# Arduino-DRA818V-TX.net
KiCad netlist of a schematic drawn in EAGLE
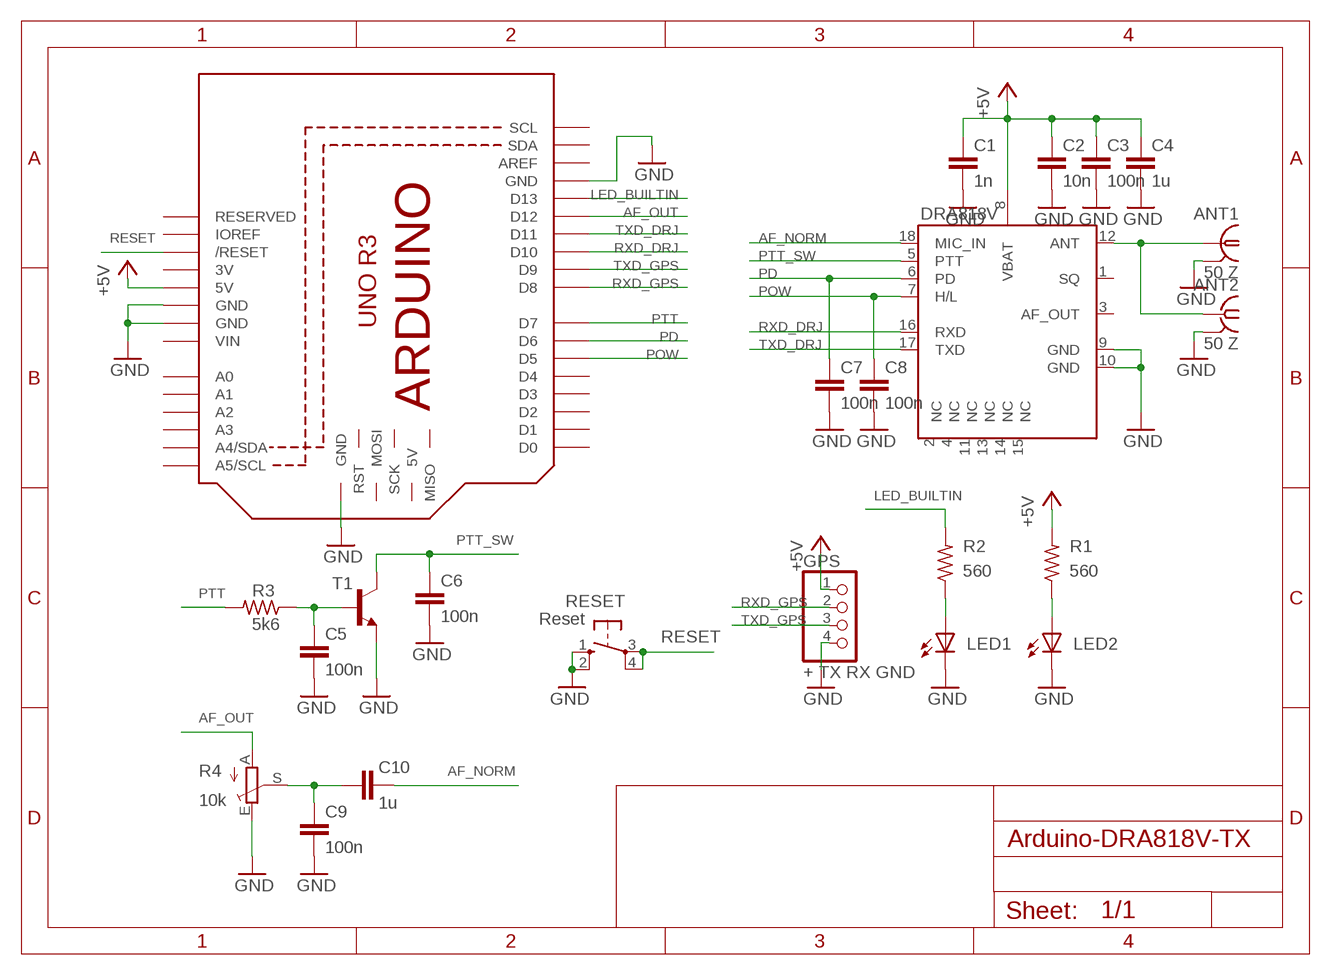
[diagram p0: schematic, sheet 1]

(export (version "E")
  (design (tool "Eeschema 10.0.6"))
  (components
    (comp (ref "ANT1")
      (value "50 Z")
      (footprint "eagle-import:LTI-SASF54GT")
      (libsource (lib "eagle-import") (part "LTI-SASF54GT"))
    )
    (comp (ref "ANT2")
      (value "50 Z")
      (footprint "eagle-import:J502-ND-142-0701-801_806")
      (fields (field (name "MF") "JOHNSON COMPONENTS") (field (name "MPN") "142-0701-801"))
      (libsource (lib "eagle-import") (part "SMA-142-0701-801/806"))
    )
    (comp (ref "C1")
      (value "1n")
      (footprint "eagle-import:C0805")
      (libsource (lib "eagle-import") (part "C-EUC0805"))
    )
    (comp (ref "C2")
      (value "10n")
      (footprint "eagle-import:C0805")
      (libsource (lib "eagle-import") (part "C-EUC0805"))
    )
    (comp (ref "C3")
      (value "100n")
      (footprint "eagle-import:C0805")
      (libsource (lib "eagle-import") (part "C-EUC0805"))
    )
    (comp (ref "C4")
      (value "1u")
      (footprint "eagle-import:C0805")
      (libsource (lib "eagle-import") (part "C-EUC0805"))
    )
    (comp (ref "C5")
      (value "100n")
      (footprint "eagle-import:C0805")
      (libsource (lib "eagle-import") (part "C-EUC0805"))
    )
    (comp (ref "C6")
      (value "100n")
      (footprint "eagle-import:C0805")
      (libsource (lib "eagle-import") (part "C-EUC0805"))
    )
    (comp (ref "C7")
      (value "100n")
      (footprint "eagle-import:C0805")
      (libsource (lib "eagle-import") (part "C-EUC0805"))
    )
    (comp (ref "C8")
      (value "100n")
      (footprint "eagle-import:C0805")
      (libsource (lib "eagle-import") (part "C-EUC0805"))
    )
    (comp (ref "C9")
      (value "100n")
      (footprint "eagle-import:C0805")
      (libsource (lib "eagle-import") (part "C-EUC0805"))
    )
    (comp (ref "C10")
      (value "1u")
      (footprint "eagle-import:C0805")
      (libsource (lib "eagle-import") (part "C-EUC0805"))
    )
    (comp (ref "DRA818V")
      (value "DRA818A")
      (footprint "eagle-import:DRA818A")
      (libsource (lib "eagle-import") (part "DRA818A"))
    )
    (comp (ref "GPS")
      (value "+ TX RX GND")
      (footprint "eagle-import:1X04")
      (libsource (lib "eagle-import") (part "PINHD-1X4"))
    )
    (comp (ref "LED1")
      (value "LED3MM")
      (footprint "eagle-import:LED3MM")
      (libsource (lib "eagle-import") (part "LED3MM"))
    )
    (comp (ref "LED2")
      (value "LED3MM")
      (footprint "eagle-import:LED3MM")
      (libsource (lib "eagle-import") (part "LED3MM"))
    )
    (comp (ref "M1")
      (value "ARDUINO_R3_ICSP")
      (footprint "eagle-import:ARDUINOR3_ICSP")
      (libsource (lib "eagle-import") (part "ARDUINO_R3_ICSP"))
    )
    (comp (ref "R1")
      (value "560")
      (footprint "eagle-import:R0805")
      (libsource (lib "eagle-import") (part "R-US_R0805"))
    )
    (comp (ref "R2")
      (value "560")
      (footprint "eagle-import:R0805")
      (libsource (lib "eagle-import") (part "R-US_R0805"))
    )
    (comp (ref "R3")
      (value "5k6")
      (footprint "eagle-import:R0805")
      (libsource (lib "eagle-import") (part "R-US_R0805"))
    )
    (comp (ref "R4")
      (value "10k")
      (footprint "eagle-import:CA6V")
      (libsource (lib "eagle-import") (part "TRIM_EU-CA6V"))
    )
    (comp (ref "RESET")
      (value "Reset")
      (footprint "eagle-import:B3F-10XX")
      (fields (field (name "MPN") "B3F-1000"))
      (libsource (lib "eagle-import") (part "10-XX"))
    )
    (comp (ref "T1")
      (value "MMBT3904LT1-NPN-SOT23-BEC")
      (footprint "eagle-import:SOT23-BEC")
      (libsource (lib "eagle-import") (part "-NPN-SOT23-BECMMBT3904LT1"))
    )
  )
  (nets
    (net (code "1") (name "+5V") (class "Default")
      (node (ref "C1") (pin "1") (pinfunction "1_1") (pintype "passive"))
      (node (ref "C2") (pin "1") (pinfunction "1_1") (pintype "passive"))
      (node (ref "C3") (pin "1") (pinfunction "1_1") (pintype "passive"))
      (node (ref "C4") (pin "1") (pinfunction "1_1") (pintype "passive"))
      (node (ref "DRA818V") (pin "8") (pinfunction "VBAT_8") (pintype "bidirectional"))
      (node (ref "GPS") (pin "1") (pinfunction "1_1") (pintype "passive"))
      (node (ref "M1") (pin "5V") (pinfunction "5V_5V") (pintype "power_in"))
      (node (ref "R1") (pin "2") (pinfunction "2_2") (pintype "passive"))
    )
    (net (code "2") (name "/3V") (class "Default")
      (node (ref "M1") (pin "3V") (pinfunction "3V_3V") (pintype "power_in"))
    )
    (net (code "3") (name "/AF_NORM") (class "Default")
      (node (ref "C10") (pin "2") (pinfunction "2_2") (pintype "passive"))
      (node (ref "DRA818V") (pin "18") (pinfunction "MIC_IN_18") (pintype "bidirectional"))
    )
    (net (code "4") (name "/AF_OUT") (class "Default")
      (node (ref "M1") (pin "D12") (pinfunction "D12_D12") (pintype "bidirectional"))
      (node (ref "R4") (pin "A") (pinfunction "A_A") (pintype "passive"))
    )
    (net (code "5") (name "/LED_BUILTIN") (class "Default")
      (node (ref "M1") (pin "D13") (pinfunction "D13_D13") (pintype "bidirectional"))
      (node (ref "R2") (pin "2") (pinfunction "2_2") (pintype "passive"))
    )
    (net (code "6") (name "/PD") (class "Default")
      (node (ref "C7") (pin "1") (pinfunction "1_1") (pintype "passive"))
      (node (ref "DRA818V") (pin "6") (pinfunction "PD_6") (pintype "bidirectional"))
      (node (ref "M1") (pin "D6") (pinfunction "D6_D6") (pintype "bidirectional"))
    )
    (net (code "7") (name "/POW") (class "Default")
      (node (ref "C8") (pin "1") (pinfunction "1_1") (pintype "passive"))
      (node (ref "DRA818V") (pin "7") (pinfunction "H/L_7") (pintype "bidirectional"))
      (node (ref "M1") (pin "D5") (pinfunction "D5_D5") (pintype "bidirectional"))
    )
    (net (code "8") (name "/PTT") (class "Default")
      (node (ref "M1") (pin "D7") (pinfunction "D7_D7") (pintype "bidirectional"))
      (node (ref "R3") (pin "2") (pinfunction "2_2") (pintype "passive"))
    )
    (net (code "9") (name "/PTT_SW") (class "Default")
      (node (ref "C6") (pin "1") (pinfunction "1_1") (pintype "passive"))
      (node (ref "DRA818V") (pin "5") (pinfunction "PTT_5") (pintype "bidirectional"))
      (node (ref "T1") (pin "C") (pinfunction "C_C") (pintype "passive"))
    )
    (net (code "10") (name "/RESET") (class "Default")
      (node (ref "M1") (pin "RESET") (pinfunction "/RESET_RESET") (pintype "bidirectional"))
      (node (ref "RESET") (pin "3") (pinfunction "P_3") (pintype "passive"))
      (node (ref "RESET") (pin "4") (pinfunction "P1_4") (pintype "passive"))
    )
    (net (code "11") (name "/RXD_DRJ") (class "Default")
      (node (ref "DRA818V") (pin "16") (pinfunction "RXD_16") (pintype "bidirectional"))
      (node (ref "M1") (pin "D10") (pinfunction "D10_D10") (pintype "bidirectional"))
    )
    (net (code "12") (name "/RXD_GPS") (class "Default")
      (node (ref "GPS") (pin "2") (pinfunction "2_2") (pintype "passive"))
      (node (ref "M1") (pin "D8") (pinfunction "D8_D8") (pintype "bidirectional"))
    )
    (net (code "13") (name "/TXD_DRJ") (class "Default")
      (node (ref "DRA818V") (pin "17") (pinfunction "TXD_17") (pintype "bidirectional"))
      (node (ref "M1") (pin "D11") (pinfunction "D11_D11") (pintype "bidirectional"))
    )
    (net (code "14") (name "/TXD_GPS") (class "Default")
      (node (ref "GPS") (pin "3") (pinfunction "3_3") (pintype "passive"))
      (node (ref "M1") (pin "D9") (pinfunction "D9_D9") (pintype "bidirectional"))
    )
    (net (code "15") (name "/VIN") (class "Default")
      (node (ref "M1") (pin "VIN") (pinfunction "VIN_VIN") (pintype "power_in"))
    )
    (net (code "16") (name "GND") (class "Default")
      (node (ref "ANT1") (pin "2") (pinfunction "2_2") (pintype "passive"))
      (node (ref "ANT1") (pin "3") (pinfunction "2_3") (pintype "passive"))
      (node (ref "ANT1") (pin "4") (pinfunction "2_4") (pintype "passive"))
      (node (ref "ANT1") (pin "5") (pinfunction "2_5") (pintype "passive"))
      (node (ref "ANT2") (pin "G@1") (pinfunction "2_G@1") (pintype "passive"))
      (node (ref "ANT2") (pin "G@2") (pinfunction "2_G@2") (pintype "passive"))
      (node (ref "ANT2") (pin "G@3") (pinfunction "2_G@3") (pintype "passive"))
      (node (ref "ANT2") (pin "G@4") (pinfunction "2_G@4") (pintype "passive"))
      (node (ref "C1") (pin "2") (pinfunction "2_2") (pintype "passive"))
      (node (ref "C2") (pin "2") (pinfunction "2_2") (pintype "passive"))
      (node (ref "C3") (pin "2") (pinfunction "2_2") (pintype "passive"))
      (node (ref "C4") (pin "2") (pinfunction "2_2") (pintype "passive"))
      (node (ref "C5") (pin "2") (pinfunction "2_2") (pintype "passive"))
      (node (ref "C6") (pin "2") (pinfunction "2_2") (pintype "passive"))
      (node (ref "C7") (pin "2") (pinfunction "2_2") (pintype "passive"))
      (node (ref "C8") (pin "2") (pinfunction "2_2") (pintype "passive"))
      (node (ref "C9") (pin "2") (pinfunction "2_2") (pintype "passive"))
      (node (ref "DRA818V") (pin "10") (pinfunction "GND_10") (pintype "bidirectional"))
      (node (ref "DRA818V") (pin "9") (pinfunction "GND_9") (pintype "bidirectional"))
      (node (ref "GPS") (pin "4") (pinfunction "4_4") (pintype "passive"))
      (node (ref "LED1") (pin "K") (pinfunction "C_K") (pintype "passive"))
      (node (ref "LED2") (pin "K") (pinfunction "C_K") (pintype "passive"))
      (node (ref "M1") (pin "GND") (pinfunction "GND_GND") (pintype "power_in"))
      (node (ref "M1") (pin "GND@1") (pinfunction "GND_GND@1") (pintype "power_in"))
      (node (ref "M1") (pin "GND@2") (pinfunction "GND_GND@2") (pintype "passive"))
      (node (ref "M1") (pin "GND@3") (pinfunction "GND_GND@3") (pintype "power_in"))
      (node (ref "R4") (pin "E") (pinfunction "E_E") (pintype "passive"))
      (node (ref "RESET") (pin "1") (pinfunction "S_1") (pintype "passive"))
      (node (ref "RESET") (pin "2") (pinfunction "S1_2") (pintype "passive"))
      (node (ref "T1") (pin "E") (pinfunction "E_E") (pintype "passive"))
    )
    (net (code "17") (name "Net-(C5-Pad1)") (class "Default")
      (node (ref "C5") (pin "1") (pinfunction "1_1") (pintype "passive"))
      (node (ref "R3") (pin "1") (pinfunction "1_1") (pintype "passive"))
      (node (ref "T1") (pin "B") (pinfunction "B_B") (pintype "passive"))
    )
    (net (code "18") (name "Net-(C10-Pad1)") (class "Default")
      (node (ref "C10") (pin "1") (pinfunction "1_1") (pintype "passive"))
      (node (ref "C9") (pin "1") (pinfunction "1_1") (pintype "passive"))
      (node (ref "R4") (pin "S") (pinfunction "S_S") (pintype "passive"))
    )
    (net (code "19") (name "Net-(DRA818V-ANT)") (class "Default")
      (node (ref "ANT1") (pin "1") (pinfunction "1_1") (pintype "passive"))
      (node (ref "ANT2") (pin "1") (pinfunction "1_1") (pintype "passive"))
      (node (ref "DRA818V") (pin "12") (pinfunction "ANT_12") (pintype "bidirectional"))
    )
    (net (code "20") (name "Net-(LED1-PadA)") (class "Default")
      (node (ref "LED1") (pin "A") (pinfunction "A_A") (pintype "passive"))
      (node (ref "R2") (pin "1") (pinfunction "1_1") (pintype "passive"))
    )
    (net (code "21") (name "Net-(LED2-PadA)") (class "Default")
      (node (ref "LED2") (pin "A") (pinfunction "A_A") (pintype "passive"))
      (node (ref "R1") (pin "1") (pinfunction "1_1") (pintype "passive"))
    )
    (net (code "22") (name "unconnected-(DRA818V-AF_OUT-Pad3)") (class "Default")
      (node (ref "DRA818V") (pin "3") (pinfunction "AF_OUT_3") (pintype "bidirectional"))
    )
    (net (code "23") (name "unconnected-(DRA818V-NC-Pad2)") (class "Default")
      (node (ref "DRA818V") (pin "2") (pinfunction "NC_2") (pintype "bidirectional"))
    )
    (net (code "24") (name "unconnected-(DRA818V-NC-Pad4)") (class "Default")
      (node (ref "DRA818V") (pin "4") (pinfunction "NC_4") (pintype "bidirectional"))
    )
    (net (code "25") (name "unconnected-(DRA818V-NC-Pad11)") (class "Default")
      (node (ref "DRA818V") (pin "11") (pinfunction "NC_11") (pintype "bidirectional"))
    )
    (net (code "26") (name "unconnected-(DRA818V-NC-Pad13)") (class "Default")
      (node (ref "DRA818V") (pin "13") (pinfunction "NC_13") (pintype "bidirectional"))
    )
    (net (code "27") (name "unconnected-(DRA818V-NC-Pad14)") (class "Default")
      (node (ref "DRA818V") (pin "14") (pinfunction "NC_14") (pintype "bidirectional"))
    )
    (net (code "28") (name "unconnected-(DRA818V-NC-Pad15)") (class "Default")
      (node (ref "DRA818V") (pin "15") (pinfunction "NC_15") (pintype "bidirectional"))
    )
    (net (code "29") (name "unconnected-(DRA818V-SQ-Pad1)") (class "Default")
      (node (ref "DRA818V") (pin "1") (pinfunction "SQ_1") (pintype "bidirectional"))
    )
    (net (code "30") (name "unconnected-(M1-5V-Pad5V_ICSP)") (class "Default")
      (node (ref "M1") (pin "5V_ICSP") (pinfunction "5V_5V_ICSP") (pintype "passive"))
    )
    (net (code "31") (name "unconnected-(M1-A4{slash}SDA-PadA4)") (class "Default")
      (node (ref "M1") (pin "A4") (pinfunction "A4/SDA_A4") (pintype "bidirectional"))
    )
    (net (code "32") (name "unconnected-(M1-A5{slash}SCL-PadA5)") (class "Default")
      (node (ref "M1") (pin "A5") (pinfunction "A5/SCL_A5") (pintype "bidirectional"))
    )
    (net (code "33") (name "unconnected-(M1-PadA0)") (class "Default")
      (node (ref "M1") (pin "A0") (pinfunction "A0_A0") (pintype "bidirectional"))
    )
    (net (code "34") (name "unconnected-(M1-PadA1)") (class "Default")
      (node (ref "M1") (pin "A1") (pinfunction "A1_A1") (pintype "bidirectional"))
    )
    (net (code "35") (name "unconnected-(M1-PadA2)") (class "Default")
      (node (ref "M1") (pin "A2") (pinfunction "A2_A2") (pintype "bidirectional"))
    )
    (net (code "36") (name "unconnected-(M1-PadA3)") (class "Default")
      (node (ref "M1") (pin "A3") (pinfunction "A3_A3") (pintype "bidirectional"))
    )
    (net (code "37") (name "unconnected-(M1-PadAREF)") (class "Default")
      (node (ref "M1") (pin "AREF") (pinfunction "AREF_AREF") (pintype "bidirectional"))
    )
    (net (code "38") (name "unconnected-(M1-PadD0)") (class "Default")
      (node (ref "M1") (pin "D0") (pinfunction "D0_D0") (pintype "bidirectional"))
    )
    (net (code "39") (name "unconnected-(M1-PadD1)") (class "Default")
      (node (ref "M1") (pin "D1") (pinfunction "D1_D1") (pintype "bidirectional"))
    )
    (net (code "40") (name "unconnected-(M1-PadD2)") (class "Default")
      (node (ref "M1") (pin "D2") (pinfunction "D2_D2") (pintype "bidirectional"))
    )
    (net (code "41") (name "unconnected-(M1-PadD3)") (class "Default")
      (node (ref "M1") (pin "D3") (pinfunction "D3_D3") (pintype "bidirectional"))
    )
    (net (code "42") (name "unconnected-(M1-PadD4)") (class "Default")
      (node (ref "M1") (pin "D4") (pinfunction "D4_D4") (pintype "bidirectional"))
    )
    (net (code "43") (name "unconnected-(M1-PadIOREF)") (class "Default")
      (node (ref "M1") (pin "IOREF") (pinfunction "IOREF_IOREF") (pintype "output"))
    )
    (net (code "44") (name "unconnected-(M1-PadMISO)") (class "Default")
      (node (ref "M1") (pin "MISO") (pinfunction "MISO_MISO") (pintype "passive"))
    )
    (net (code "45") (name "unconnected-(M1-PadMOSI)") (class "Default")
      (node (ref "M1") (pin "MOSI") (pinfunction "MOSI_MOSI") (pintype "passive"))
    )
    (net (code "46") (name "unconnected-(M1-PadRESERVED)") (class "Default")
      (node (ref "M1") (pin "RESERVED") (pinfunction "RESERVED_RESERVED") (pintype "no_connect"))
    )
    (net (code "47") (name "unconnected-(M1-PadSCK)") (class "Default")
      (node (ref "M1") (pin "SCK") (pinfunction "SCK_SCK") (pintype "passive"))
    )
    (net (code "48") (name "unconnected-(M1-PadSCL)") (class "Default")
      (node (ref "M1") (pin "SCL") (pinfunction "SCL_SCL") (pintype "bidirectional"))
    )
    (net (code "49") (name "unconnected-(M1-PadSDA)") (class "Default")
      (node (ref "M1") (pin "SDA") (pinfunction "SDA_SDA") (pintype "bidirectional"))
    )
    (net (code "50") (name "unconnected-(M1-RST-PadRESET_ICSP)") (class "Default")
      (node (ref "M1") (pin "RESET_ICSP") (pinfunction "RST_RESET_ICSP") (pintype "passive"))
    )
  )
)
